# bGeigieNanoKit_V1_1r4a.net
KiCad netlist of a schematic drawn in EAGLE
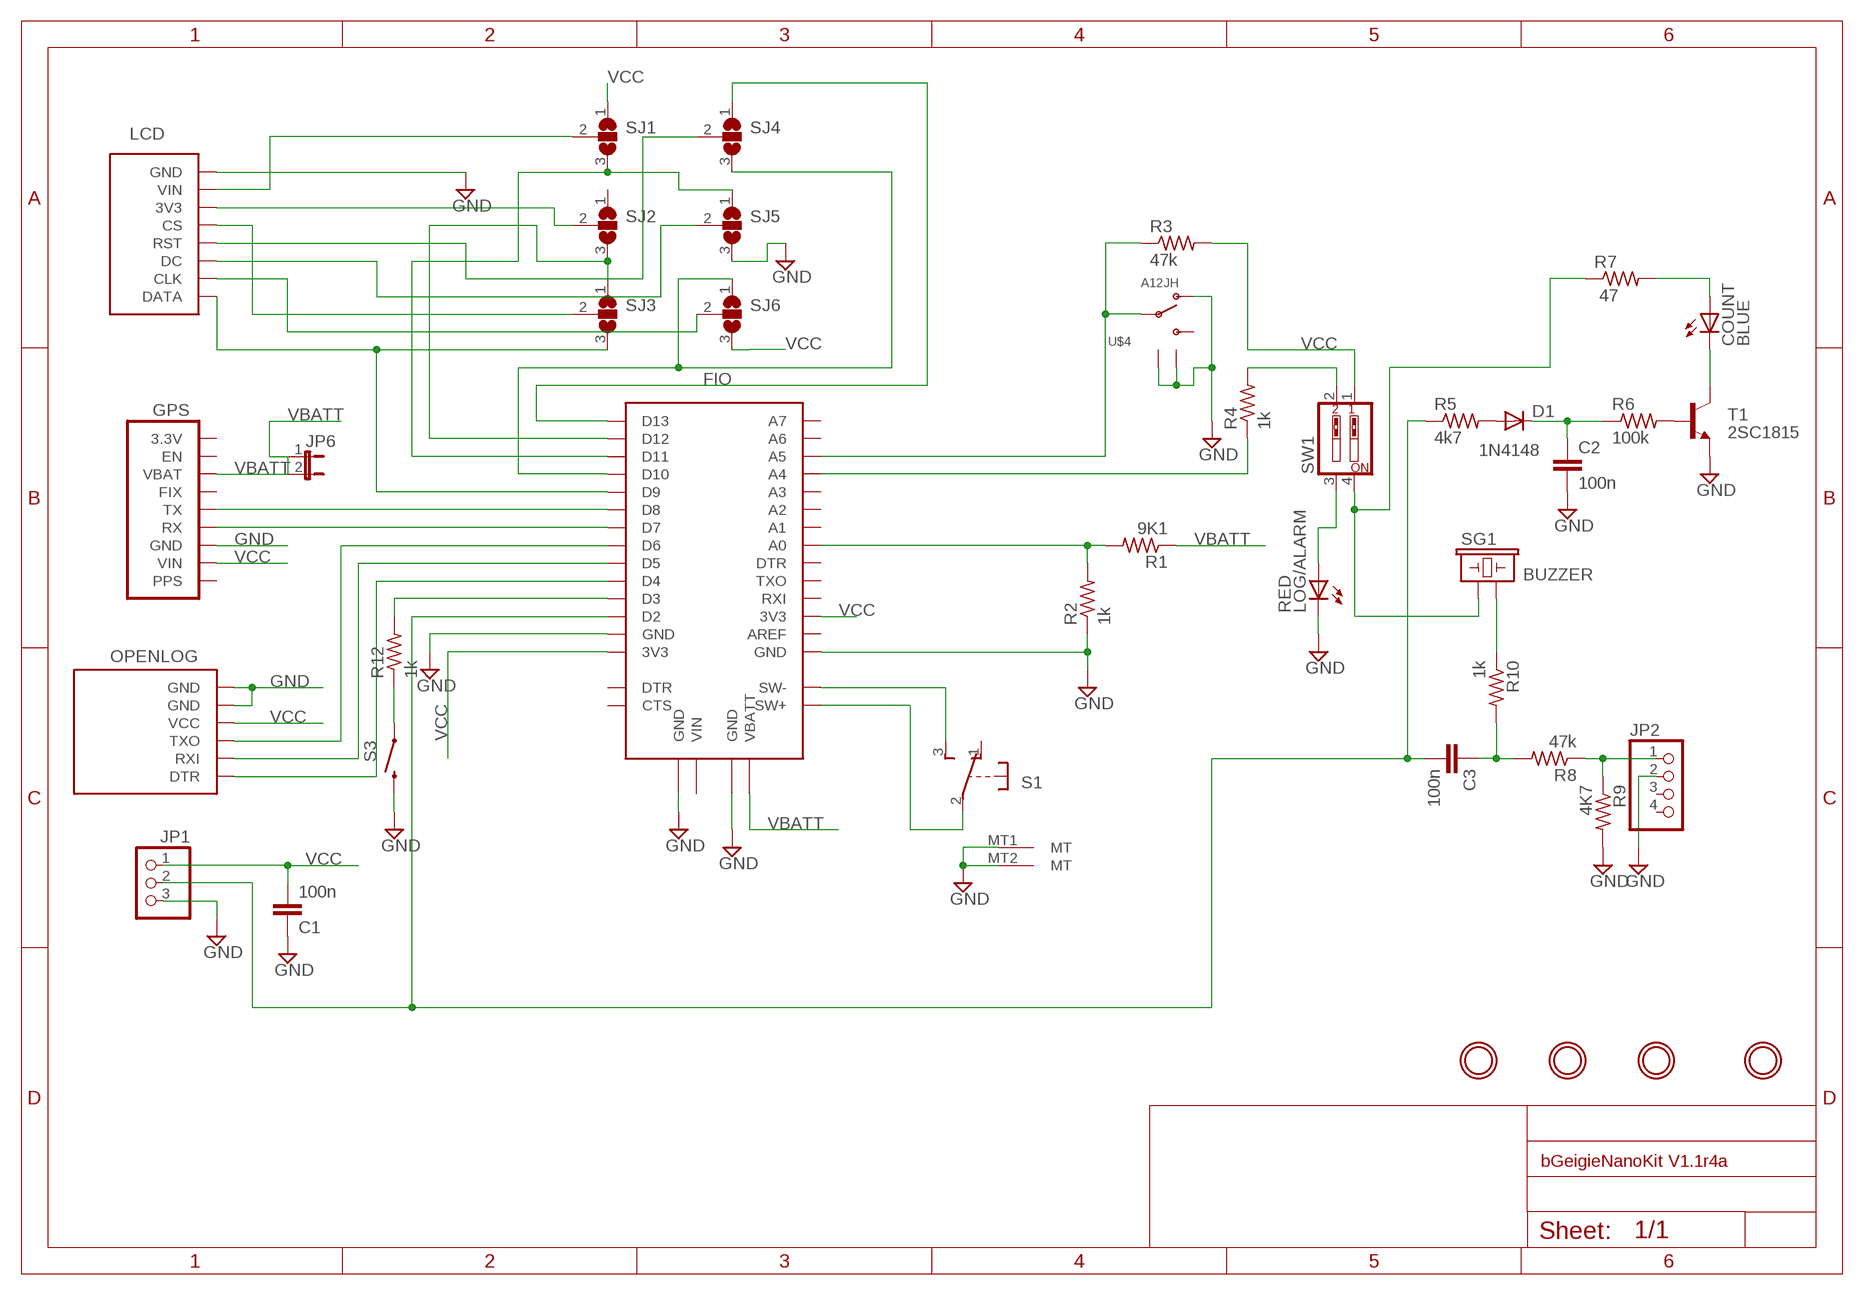
[diagram p0: schematic, sheet 1]

(export (version "E")
  (design (tool "Eeschema 10.0.6"))
  (components
    (comp (ref "C1")
      (value "100n")
      (footprint "eagle-import:C025-024X044")
      (libsource (lib "eagle-import") (part "C-EU025-024X044"))
    )
    (comp (ref "C2")
      (value "100n")
      (footprint "eagle-import:C025-024X044")
      (libsource (lib "eagle-import") (part "C-EU025-024X044"))
    )
    (comp (ref "C3")
      (value "100n")
      (footprint "eagle-import:C025-024X044")
      (libsource (lib "eagle-import") (part "C-EU025-024X044"))
    )
    (comp (ref "COUNT")
      (value "BLUE")
      (footprint "eagle-import:LED3MM")
      (libsource (lib "eagle-import") (part "LED3MM"))
    )
    (comp (ref "D1")
      (value "1N4148")
      (footprint "eagle-import:DO35-7")
      (fields (field (name "D1") "1N4148"))
      (libsource (lib "eagle-import") (part "1N4148DO35-7"))
    )
    (comp (ref "FIO")
      (value "FIO_SOCKETBOT")
      (footprint "eagle-import:FIO_V23_SOCKET_BOT")
      (libsource (lib "eagle-import") (part "FIO_SOCKETBOT"))
    )
    (comp (ref "GPS")
      (value "ULTIMATE_GPSTOP")
      (footprint "eagle-import:ULTIMATE_GPS_V3_TOP")
      (libsource (lib "eagle-import") (part "ULTIMATE_GPSTOP"))
    )
    (comp (ref "JP1")
      (value "PINHD-1X3/90")
      (footprint "eagle-import:1X03_90")
      (libsource (lib "eagle-import") (part "PINHD-1X3/90"))
    )
    (comp (ref "JP2")
      (value "HEADER-1X4ROUND")
      (footprint "eagle-import:1X04_ROUND")
      (libsource (lib "eagle-import") (part "HEADER-1X4ROUND"))
    )
    (comp (ref "JP6")
      (value "JUMPER-2SMD-NC")
      (footprint "eagle-import:SJ_2S")
      (libsource (lib "eagle-import") (part "JUMPER-2SMD-NC"))
    )
    (comp (ref "LCD")
      (value "SSD1306_128X64_V2_LCD1.3IN_LEVER")
      (footprint "eagle-import:SSD1306_128X64_1.3IN_LCD_LEVER")
      (libsource (lib "eagle-import") (part "SSD1306_128X64_V2_LCD1.3IN_LEVER"))
    )
    (comp (ref "LOG/ALARM")
      (value "RED")
      (footprint "eagle-import:LED3MM")
      (libsource (lib "eagle-import") (part "LED3MM"))
    )
    (comp (ref "OPENLOG")
      (value "OPENLOG")
      (footprint "eagle-import:OPENLOG")
      (libsource (lib "eagle-import") (part "OPENLOG"))
    )
    (comp (ref "R1")
      (value "9K1")
      (footprint "eagle-import:0207_10")
      (libsource (lib "eagle-import") (part "R-US_0207/10"))
    )
    (comp (ref "R2")
      (value "1k")
      (footprint "eagle-import:0207_10")
      (libsource (lib "eagle-import") (part "R-US_0207/10"))
    )
    (comp (ref "R3")
      (value "47k")
      (footprint "eagle-import:0207_10")
      (libsource (lib "eagle-import") (part "R-US_0207/10"))
    )
    (comp (ref "R4")
      (value "1k")
      (footprint "eagle-import:0207_10")
      (libsource (lib "eagle-import") (part "R-US_0207/10"))
    )
    (comp (ref "R5")
      (value "4k7")
      (footprint "eagle-import:0207_10")
      (libsource (lib "eagle-import") (part "R-US_0207/10"))
    )
    (comp (ref "R6")
      (value "100k")
      (footprint "eagle-import:0207_10")
      (libsource (lib "eagle-import") (part "R-US_0207/10"))
    )
    (comp (ref "R7")
      (value "47")
      (footprint "eagle-import:0207_10")
      (libsource (lib "eagle-import") (part "R-US_0207/10"))
    )
    (comp (ref "R8")
      (value "47k")
      (footprint "eagle-import:0207_10")
      (libsource (lib "eagle-import") (part "R-US_0207/10"))
    )
    (comp (ref "R9")
      (value "4K7")
      (footprint "eagle-import:0207_10")
      (libsource (lib "eagle-import") (part "R-US_0207/10"))
    )
    (comp (ref "R10")
      (value "1k")
      (footprint "eagle-import:0207_10")
      (libsource (lib "eagle-import") (part "R-US_0207/10"))
    )
    (comp (ref "R12")
      (value "1k")
      (footprint "eagle-import:0207_10")
      (libsource (lib "eagle-import") (part "R-US_0207/10"))
    )
    (comp (ref "S1")
      (value "S1")
      (footprint "eagle-import:EG1206")
      (libsource (lib "eagle-import") (part "EG1206"))
    )
    (comp (ref "S3")
      (value "SWITCH-MOMENTARY-2PTH")
      (footprint "eagle-import:TACTILE-PTH")
      (libsource (lib "eagle-import") (part "SWITCH-MOMENTARY-2PTH"))
    )
    (comp (ref "SG1")
      (value "BUZZER")
      (footprint "eagle-import:BUZZER-12MM")
      (libsource (lib "eagle-import") (part "BUZZERPTH"))
    )
    (comp (ref "SJ1")
      (value "SJ2W")
      (footprint "eagle-import:SJ_2")
      (libsource (lib "eagle-import") (part "SJ2W"))
    )
    (comp (ref "SJ2")
      (value "SJ2W")
      (footprint "eagle-import:SJ_2")
      (libsource (lib "eagle-import") (part "SJ2W"))
    )
    (comp (ref "SJ3")
      (value "SJ2W")
      (footprint "eagle-import:SJ_2")
      (libsource (lib "eagle-import") (part "SJ2W"))
    )
    (comp (ref "SJ4")
      (value "SJ2W")
      (footprint "eagle-import:SJ_2")
      (libsource (lib "eagle-import") (part "SJ2W"))
    )
    (comp (ref "SJ5")
      (value "SJ2W")
      (footprint "eagle-import:SJ_2")
      (libsource (lib "eagle-import") (part "SJ2W"))
    )
    (comp (ref "SJ6")
      (value "SJ2W")
      (footprint "eagle-import:SJ_2")
      (libsource (lib "eagle-import") (part "SJ2W"))
    )
    (comp (ref "SW1")
      (value "SW_DIP-2")
      (footprint "eagle-import:EDG-02")
      (libsource (lib "eagle-import") (part "SW_DIP-2"))
    )
    (comp (ref "T1")
      (value "2SC1815")
      (footprint "eagle-import:TO92-ECB")
      (libsource (lib "eagle-import") (part "2SC1815"))
    )
    (comp (ref "U$4")
      (value "A12JH")
      (footprint "eagle-import:A12AH")
      (libsource (lib "eagle-import") (part "A12JH"))
    )
    (comp (ref "U$6")
      (value "MOUNTINGHOLE3.0THIN")
      (footprint "eagle-import:MOUNTINGHOLE_3.0_PLATEDTHIN")
      (libsource (lib "eagle-import") (part "MOUNTINGHOLE3.0THIN"))
    )
    (comp (ref "U$7")
      (value "MOUNTINGHOLE3.0THIN")
      (footprint "eagle-import:MOUNTINGHOLE_3.0_PLATEDTHIN")
      (libsource (lib "eagle-import") (part "MOUNTINGHOLE3.0THIN"))
    )
    (comp (ref "U$8")
      (value "MOUNTINGHOLE3.0THIN")
      (footprint "eagle-import:MOUNTINGHOLE_3.0_PLATEDTHIN")
      (libsource (lib "eagle-import") (part "MOUNTINGHOLE3.0THIN"))
    )
    (comp (ref "U$9")
      (value "MOUNTINGHOLE3.0THIN")
      (footprint "eagle-import:MOUNTINGHOLE_3.0_PLATEDTHIN")
      (libsource (lib "eagle-import") (part "MOUNTINGHOLE3.0THIN"))
    )
  )
  (nets
    (net (code "1") (name "/3.3V") (class "Default")
      (node (ref "GPS") (pin "JP1$9") (pinfunction "3.3V_JP1$9") (pintype "power_in"))
    )
    (net (code "2") (name "/VBATT") (class "Default")
      (node (ref "FIO") (pin "JP2$2") (pinfunction "VBATT_JP2$2") (pintype "bidirectional"))
      (node (ref "GPS") (pin "JP1$7") (pinfunction "VBAT_JP1$7") (pintype "power_in"))
      (node (ref "JP6") (pin "1") (pinfunction "1_1") (pintype "passive"))
      (node (ref "JP6") (pin "2") (pinfunction "2_2") (pintype "passive"))
      (node (ref "R1") (pin "1") (pinfunction "1_1") (pintype "passive"))
    )
    (net (code "3") (name "/VCC") (class "Default")
      (node (ref "C1") (pin "2") (pinfunction "2_2") (pintype "passive"))
      (node (ref "FIO") (pin "JP1$1") (pinfunction "3V3_JP1$1") (pintype "power_in"))
      (node (ref "FIO") (pin "JP5$3") (pinfunction "3V3_JP5$3") (pintype "power_in"))
      (node (ref "GPS") (pin "JP1$2") (pinfunction "VIN_JP1$2") (pintype "power_in"))
      (node (ref "JP1") (pin "1") (pinfunction "1_1") (pintype "passive"))
      (node (ref "OPENLOG") (pin "JP1$4") (pinfunction "VCC_JP1$4") (pintype "power_in"))
      (node (ref "R3") (pin "2") (pinfunction "2_2") (pintype "passive"))
      (node (ref "SJ1") (pin "1") (pinfunction "1_1") (pintype "passive"))
      (node (ref "SJ6") (pin "3") (pinfunction "3_3") (pintype "passive"))
      (node (ref "SW1") (pin "1") (pinfunction "1_1") (pintype "passive"))
    )
    (net (code "4") (name "GND") (class "Default")
      (node (ref "C1") (pin "1") (pinfunction "1_1") (pintype "passive"))
      (node (ref "C2") (pin "2") (pinfunction "2_2") (pintype "passive"))
      (node (ref "FIO") (pin "JP1$2") (pinfunction "GND_JP1$2") (pintype "power_in"))
      (node (ref "FIO") (pin "JP2$1") (pinfunction "GND_JP2$1") (pintype "bidirectional"))
      (node (ref "FIO") (pin "JP5$1") (pinfunction "GND_JP5$1") (pintype "power_in"))
      (node (ref "FIO") (pin "JP6$1") (pinfunction "GND_JP6$1") (pintype "bidirectional"))
      (node (ref "GPS") (pin "JP1$3") (pinfunction "GND_JP1$3") (pintype "power_in"))
      (node (ref "GPS") (pin "U$8$P$1") (pinfunction "GND_U$8$P$1") (pintype "power_in"))
      (node (ref "GPS") (pin "U$9$P$1") (pinfunction "GND_U$9$P$1") (pintype "power_in"))
      (node (ref "JP1") (pin "3") (pinfunction "3_3") (pintype "passive"))
      (node (ref "JP2") (pin "2") (pinfunction "2_2") (pintype "passive"))
      (node (ref "LCD") (pin "JP1$8") (pinfunction "GND_JP1$8") (pintype "power_in"))
      (node (ref "LCD") (pin "U$23$P$1") (pinfunction "GND_U$23$P$1") (pintype "power_in"))
      (node (ref "LCD") (pin "U$26$P$1") (pinfunction "GND_U$26$P$1") (pintype "power_in"))
      (node (ref "LOG/ALARM") (pin "K") (pinfunction "C_K") (pintype "passive"))
      (node (ref "OPENLOG") (pin "JP1$5") (pinfunction "GND_JP1$5") (pintype "power_in"))
      (node (ref "OPENLOG") (pin "JP1$6") (pinfunction "GND_JP1$6") (pintype "power_in"))
      (node (ref "R2") (pin "1") (pinfunction "1_1") (pintype "passive"))
      (node (ref "R9") (pin "2") (pinfunction "2_2") (pintype "passive"))
      (node (ref "S1") (pin "MT1") (pinfunction "MT_MT1") (pintype "passive"))
      (node (ref "S1") (pin "MT2") (pinfunction "MT_MT2") (pintype "passive"))
      (node (ref "S3") (pin "3") (pinfunction "2_3") (pintype "passive"))
      (node (ref "SJ5") (pin "3") (pinfunction "3_3") (pintype "passive"))
      (node (ref "T1") (pin "E") (pinfunction "E_E") (pintype "passive"))
      (node (ref "U$4") (pin "P$1") (pinfunction "P$1_P$1") (pintype "passive"))
      (node (ref "U$4") (pin "P$4") (pinfunction "GND_P$4") (pintype "power_in"))
      (node (ref "U$4") (pin "P$5") (pinfunction "GND_P$5") (pintype "power_in"))
    )
    (net (code "5") (name "Net-(C2-Pad1)") (class "Default")
      (node (ref "C2") (pin "1") (pinfunction "1_1") (pintype "passive"))
      (node (ref "D1") (pin "C") (pinfunction "C_C") (pintype "passive"))
      (node (ref "R6") (pin "1") (pinfunction "1_1") (pintype "passive"))
    )
    (net (code "6") (name "Net-(C3-Pad1)") (class "Default")
      (node (ref "C3") (pin "1") (pinfunction "1_1") (pintype "passive"))
      (node (ref "R10") (pin "2") (pinfunction "2_2") (pintype "passive"))
      (node (ref "R8") (pin "2") (pinfunction "2_2") (pintype "passive"))
    )
    (net (code "7") (name "Net-(COUNT-C)") (class "Default")
      (node (ref "COUNT") (pin "K") (pinfunction "C_K") (pintype "passive"))
      (node (ref "T1") (pin "C") (pinfunction "C_C") (pintype "passive"))
    )
    (net (code "8") (name "Net-(COUNT-PadA)") (class "Default")
      (node (ref "COUNT") (pin "A") (pinfunction "A_A") (pintype "passive"))
      (node (ref "R7") (pin "2") (pinfunction "2_2") (pintype "passive"))
    )
    (net (code "9") (name "Net-(D1-PadA)") (class "Default")
      (node (ref "D1") (pin "A") (pinfunction "A_A") (pintype "passive"))
      (node (ref "R5") (pin "2") (pinfunction "2_2") (pintype "passive"))
    )
    (net (code "10") (name "Net-(FIO-A0)") (class "Default")
      (node (ref "FIO") (pin "JP5$7") (pinfunction "A0_JP5$7") (pintype "bidirectional"))
      (node (ref "R1") (pin "2") (pinfunction "2_2") (pintype "passive"))
      (node (ref "R2") (pin "2") (pinfunction "2_2") (pintype "passive"))
    )
    (net (code "11") (name "Net-(FIO-A4)") (class "Default")
      (node (ref "FIO") (pin "JP5$11") (pinfunction "A4_JP5$11") (pintype "bidirectional"))
      (node (ref "R4") (pin "1") (pinfunction "1_1") (pintype "passive"))
    )
    (net (code "12") (name "Net-(FIO-A5)") (class "Default")
      (node (ref "FIO") (pin "JP5$12") (pinfunction "A5_JP5$12") (pintype "bidirectional"))
      (node (ref "R3") (pin "1") (pinfunction "1_1") (pintype "passive"))
      (node (ref "U$4") (pin "P$2") (pinfunction "P$2_P$2") (pintype "passive"))
    )
    (net (code "13") (name "Net-(FIO-D2)") (class "Default")
      (node (ref "C3") (pin "2") (pinfunction "2_2") (pintype "passive"))
      (node (ref "FIO") (pin "JP1$3") (pinfunction "D2_JP1$3") (pintype "bidirectional"))
      (node (ref "JP1") (pin "2") (pinfunction "2_2") (pintype "passive"))
      (node (ref "R5") (pin "1") (pinfunction "1_1") (pintype "passive"))
    )
    (net (code "14") (name "Net-(FIO-D3)") (class "Default")
      (node (ref "FIO") (pin "JP1$4") (pinfunction "D3_JP1$4") (pintype "bidirectional"))
      (node (ref "R12") (pin "2") (pinfunction "2_2") (pintype "passive"))
    )
    (net (code "15") (name "Net-(FIO-D4)") (class "Default")
      (node (ref "FIO") (pin "JP1$5") (pinfunction "D4_JP1$5") (pintype "bidirectional"))
      (node (ref "OPENLOG") (pin "JP1$1") (pinfunction "DTR_JP1$1") (pintype "input"))
    )
    (net (code "16") (name "Net-(FIO-D5)") (class "Default")
      (node (ref "FIO") (pin "JP1$6") (pinfunction "D5_JP1$6") (pintype "bidirectional"))
      (node (ref "OPENLOG") (pin "JP1$2") (pinfunction "RXI_JP1$2") (pintype "input"))
    )
    (net (code "17") (name "Net-(FIO-D6)") (class "Default")
      (node (ref "FIO") (pin "JP1$7") (pinfunction "D6_JP1$7") (pintype "bidirectional"))
      (node (ref "OPENLOG") (pin "JP1$3") (pinfunction "TXO_JP1$3") (pintype "output"))
    )
    (net (code "18") (name "Net-(FIO-D7)") (class "Default")
      (node (ref "FIO") (pin "JP1$8") (pinfunction "D7_JP1$8") (pintype "bidirectional"))
      (node (ref "GPS") (pin "JP1$4") (pinfunction "RX_JP1$4") (pintype "input"))
    )
    (net (code "19") (name "Net-(FIO-D8)") (class "Default")
      (node (ref "FIO") (pin "JP1$9") (pinfunction "D8_JP1$9") (pintype "bidirectional"))
      (node (ref "GPS") (pin "JP1$5") (pinfunction "TX_JP1$5") (pintype "output"))
    )
    (net (code "20") (name "Net-(FIO-D9)") (class "Default")
      (node (ref "FIO") (pin "JP1$10") (pinfunction "D9_JP1$10") (pintype "bidirectional"))
      (node (ref "LCD") (pin "JP1$1") (pinfunction "DATA_JP1$1") (pintype "bidirectional"))
      (node (ref "SJ3") (pin "3") (pinfunction "3_3") (pintype "passive"))
    )
    (net (code "21") (name "Net-(FIO-D10)") (class "Default")
      (node (ref "FIO") (pin "JP1$11") (pinfunction "D10_JP1$11") (pintype "bidirectional"))
      (node (ref "SJ4") (pin "3") (pinfunction "3_3") (pintype "passive"))
      (node (ref "SJ6") (pin "1") (pinfunction "1_1") (pintype "passive"))
    )
    (net (code "22") (name "Net-(FIO-D11)") (class "Default")
      (node (ref "FIO") (pin "JP1$12") (pinfunction "D11_JP1$12") (pintype "bidirectional"))
      (node (ref "SJ1") (pin "3") (pinfunction "3_3") (pintype "passive"))
      (node (ref "SJ5") (pin "1") (pinfunction "1_1") (pintype "passive"))
    )
    (net (code "23") (name "Net-(FIO-D12)") (class "Default")
      (node (ref "FIO") (pin "JP1$13") (pinfunction "D12_JP1$13") (pintype "bidirectional"))
      (node (ref "SJ2") (pin "3") (pinfunction "3_3") (pintype "passive"))
      (node (ref "SJ3") (pin "1") (pinfunction "1_1") (pintype "passive"))
    )
    (net (code "24") (name "Net-(FIO-D13)") (class "Default")
      (node (ref "FIO") (pin "JP1$14") (pinfunction "D13_JP1$14") (pintype "bidirectional"))
      (node (ref "SJ4") (pin "1") (pinfunction "1_1") (pintype "passive"))
    )
    (net (code "25") (name "Net-(FIO-SW+)") (class "Default")
      (node (ref "FIO") (pin "JP7$2") (pinfunction "SW+_JP7$2") (pintype "bidirectional"))
      (node (ref "S1") (pin "2") (pinfunction "P_2") (pintype "passive"))
    )
    (net (code "26") (name "Net-(FIO-SW-)") (class "Default")
      (node (ref "FIO") (pin "JP7$1") (pinfunction "SW-_JP7$1") (pintype "bidirectional"))
      (node (ref "S1") (pin "3") (pinfunction "S_3") (pintype "passive"))
    )
    (net (code "27") (name "Net-(JP2-Pad1)") (class "Default")
      (node (ref "JP2") (pin "1") (pinfunction "1_1") (pintype "passive"))
      (node (ref "R8") (pin "1") (pinfunction "1_1") (pintype "passive"))
      (node (ref "R9") (pin "1") (pinfunction "1_1") (pintype "passive"))
    )
    (net (code "28") (name "Net-(LCD-3V3)") (class "Default")
      (node (ref "LCD") (pin "JP1$6") (pinfunction "3V3_JP1$6") (pintype "bidirectional"))
      (node (ref "SJ2") (pin "2") (pinfunction "2_2") (pintype "passive"))
    )
    (net (code "29") (name "Net-(LCD-CLK)") (class "Default")
      (node (ref "LCD") (pin "JP1$2") (pinfunction "CLK_JP1$2") (pintype "bidirectional"))
      (node (ref "SJ6") (pin "2") (pinfunction "2_2") (pintype "passive"))
    )
    (net (code "30") (name "Net-(LCD-CS)") (class "Default")
      (node (ref "LCD") (pin "JP1$5") (pinfunction "CS_JP1$5") (pintype "bidirectional"))
      (node (ref "SJ3") (pin "2") (pinfunction "2_2") (pintype "passive"))
    )
    (net (code "31") (name "Net-(LCD-DC)") (class "Default")
      (node (ref "LCD") (pin "JP1$3") (pinfunction "DC_JP1$3") (pintype "bidirectional"))
      (node (ref "SJ5") (pin "2") (pinfunction "2_2") (pintype "passive"))
    )
    (net (code "32") (name "Net-(LCD-RST)") (class "Default")
      (node (ref "LCD") (pin "JP1$4") (pinfunction "RST_JP1$4") (pintype "bidirectional"))
      (node (ref "SJ4") (pin "2") (pinfunction "2_2") (pintype "passive"))
    )
    (net (code "33") (name "Net-(LCD-VIN)") (class "Default")
      (node (ref "LCD") (pin "JP1$7") (pinfunction "VIN_JP1$7") (pintype "power_in"))
      (node (ref "SJ1") (pin "2") (pinfunction "2_2") (pintype "passive"))
    )
    (net (code "34") (name "Net-(LOG/ALARM-PadA)") (class "Default")
      (node (ref "LOG/ALARM") (pin "A") (pinfunction "A_A") (pintype "passive"))
      (node (ref "SW1") (pin "3") (pinfunction "3_3") (pintype "passive"))
    )
    (net (code "35") (name "Net-(R4-Pad2)") (class "Default")
      (node (ref "R4") (pin "2") (pinfunction "2_2") (pintype "passive"))
      (node (ref "SW1") (pin "2") (pinfunction "2_2") (pintype "passive"))
    )
    (net (code "36") (name "Net-(R6-Pad2)") (class "Default")
      (node (ref "R6") (pin "2") (pinfunction "2_2") (pintype "passive"))
      (node (ref "T1") (pin "B") (pinfunction "B_B") (pintype "passive"))
    )
    (net (code "37") (name "Net-(R12-Pad1)") (class "Default")
      (node (ref "R12") (pin "1") (pinfunction "1_1") (pintype "passive"))
      (node (ref "S3") (pin "1") (pinfunction "1_1") (pintype "passive"))
    )
    (net (code "38") (name "Net-(SG1-1)") (class "Default")
      (node (ref "R7") (pin "1") (pinfunction "1_1") (pintype "passive"))
      (node (ref "SG1") (pin "+") (pinfunction "1_+") (pintype "passive"))
      (node (ref "SW1") (pin "4") (pinfunction "4_4") (pintype "passive"))
    )
    (net (code "39") (name "Net-(SG1-2)") (class "Default")
      (node (ref "R10") (pin "1") (pinfunction "1_1") (pintype "passive"))
      (node (ref "SG1") (pin "-") (pinfunction "2_-") (pintype "passive"))
    )
    (net (code "40") (name "unconnected-(FIO-A1-PadJP5$8)") (class "Default")
      (node (ref "FIO") (pin "JP5$8") (pinfunction "A1_JP5$8") (pintype "bidirectional"))
    )
    (net (code "41") (name "unconnected-(FIO-A2-PadJP5$9)") (class "Default")
      (node (ref "FIO") (pin "JP5$9") (pinfunction "A2_JP5$9") (pintype "bidirectional"))
    )
    (net (code "42") (name "unconnected-(FIO-A3-PadJP5$10)") (class "Default")
      (node (ref "FIO") (pin "JP5$10") (pinfunction "A3_JP5$10") (pintype "bidirectional"))
    )
    (net (code "43") (name "unconnected-(FIO-A6-PadJP5$13)") (class "Default")
      (node (ref "FIO") (pin "JP5$13") (pinfunction "A6_JP5$13") (pintype "bidirectional"))
    )
    (net (code "44") (name "unconnected-(FIO-A7-PadJP5$14)") (class "Default")
      (node (ref "FIO") (pin "JP5$14") (pinfunction "A7_JP5$14") (pintype "bidirectional"))
    )
    (net (code "45") (name "unconnected-(FIO-AREF-PadJP5$2)") (class "Default")
      (node (ref "FIO") (pin "JP5$2") (pinfunction "AREF_JP5$2") (pintype "output"))
    )
    (net (code "46") (name "unconnected-(FIO-CTS-PadJP8$1)") (class "Default")
      (node (ref "FIO") (pin "JP8$1") (pinfunction "CTS_JP8$1") (pintype "bidirectional"))
    )
    (net (code "47") (name "unconnected-(FIO-DTR-PadJP5$6)") (class "Default")
      (node (ref "FIO") (pin "JP5$6") (pinfunction "DTR_JP5$6") (pintype "input"))
    )
    (net (code "48") (name "unconnected-(FIO-DTR-PadJP9$1)") (class "Default")
      (node (ref "FIO") (pin "JP9$1") (pinfunction "DTR_JP9$1") (pintype "bidirectional"))
    )
    (net (code "49") (name "unconnected-(FIO-RXI-PadJP5$4)") (class "Default")
      (node (ref "FIO") (pin "JP5$4") (pinfunction "RXI_JP5$4") (pintype "input"))
    )
    (net (code "50") (name "unconnected-(FIO-TXO-PadJP5$5)") (class "Default")
      (node (ref "FIO") (pin "JP5$5") (pinfunction "TXO_JP5$5") (pintype "output"))
    )
    (net (code "51") (name "unconnected-(FIO-VIN-PadJP6$2)") (class "Default")
      (node (ref "FIO") (pin "JP6$2") (pinfunction "VIN_JP6$2") (pintype "bidirectional"))
    )
    (net (code "52") (name "unconnected-(GPS-EN-PadJP1$8)") (class "Default")
      (node (ref "GPS") (pin "JP1$8") (pinfunction "EN_JP1$8") (pintype "input"))
    )
    (net (code "53") (name "unconnected-(GPS-FIX-PadJP1$6)") (class "Default")
      (node (ref "GPS") (pin "JP1$6") (pinfunction "FIX_JP1$6") (pintype "output"))
    )
    (net (code "54") (name "unconnected-(GPS-PPS-PadJP1$1)") (class "Default")
      (node (ref "GPS") (pin "JP1$1") (pinfunction "PPS_JP1$1") (pintype "output"))
    )
    (net (code "55") (name "unconnected-(JP2-Pad3)") (class "Default")
      (node (ref "JP2") (pin "3") (pinfunction "3_3") (pintype "passive"))
    )
    (net (code "56") (name "unconnected-(JP2-Pad4)") (class "Default")
      (node (ref "JP2") (pin "4") (pinfunction "4_4") (pintype "passive"))
    )
    (net (code "57") (name "unconnected-(S1A-O-Pad1)") (class "Default")
      (node (ref "S1") (pin "1") (pinfunction "O_1") (pintype "passive"))
    )
    (net (code "58") (name "unconnected-(SJ2-Pad1)") (class "Default")
      (node (ref "SJ2") (pin "1") (pinfunction "1_1") (pintype "passive"))
    )
    (net (code "59") (name "unconnected-(U$4-PadP$3)") (class "Default")
      (node (ref "U$4") (pin "P$3") (pinfunction "P$3_P$3") (pintype "passive"))
    )
  )
)
